# CM5_IO.net
KiCad netlist of a schematic drawn in Altium Designer
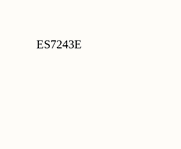
[diagram p0: CM5 + IO.SchDoc, top left]
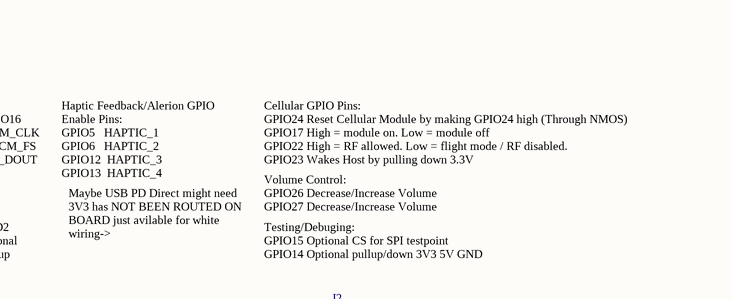
[diagram p1: CM5 + IO.SchDoc, top right]
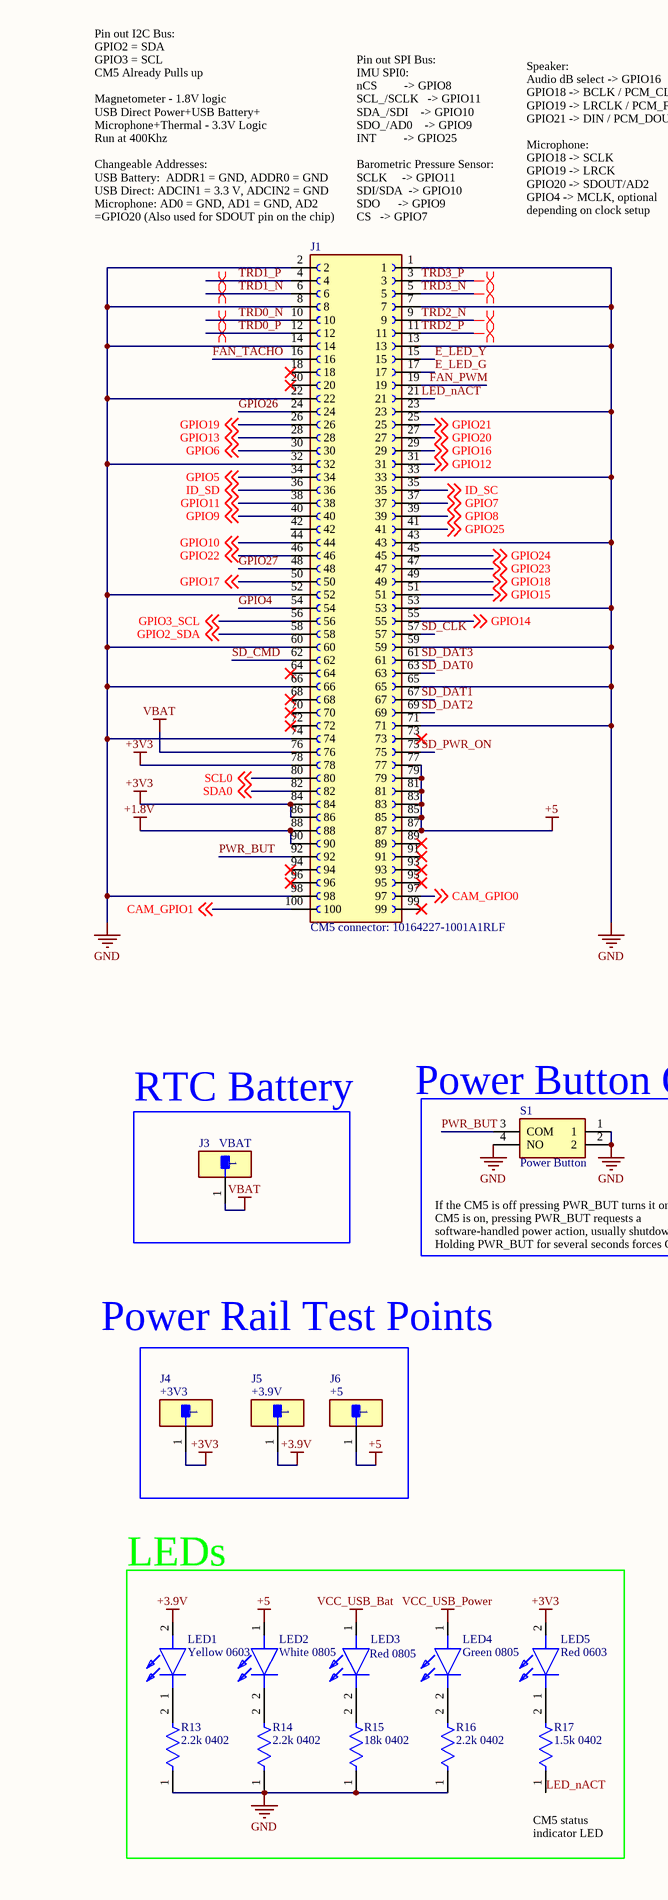
[diagram p2: CM5 + IO.SchDoc, bottom left]
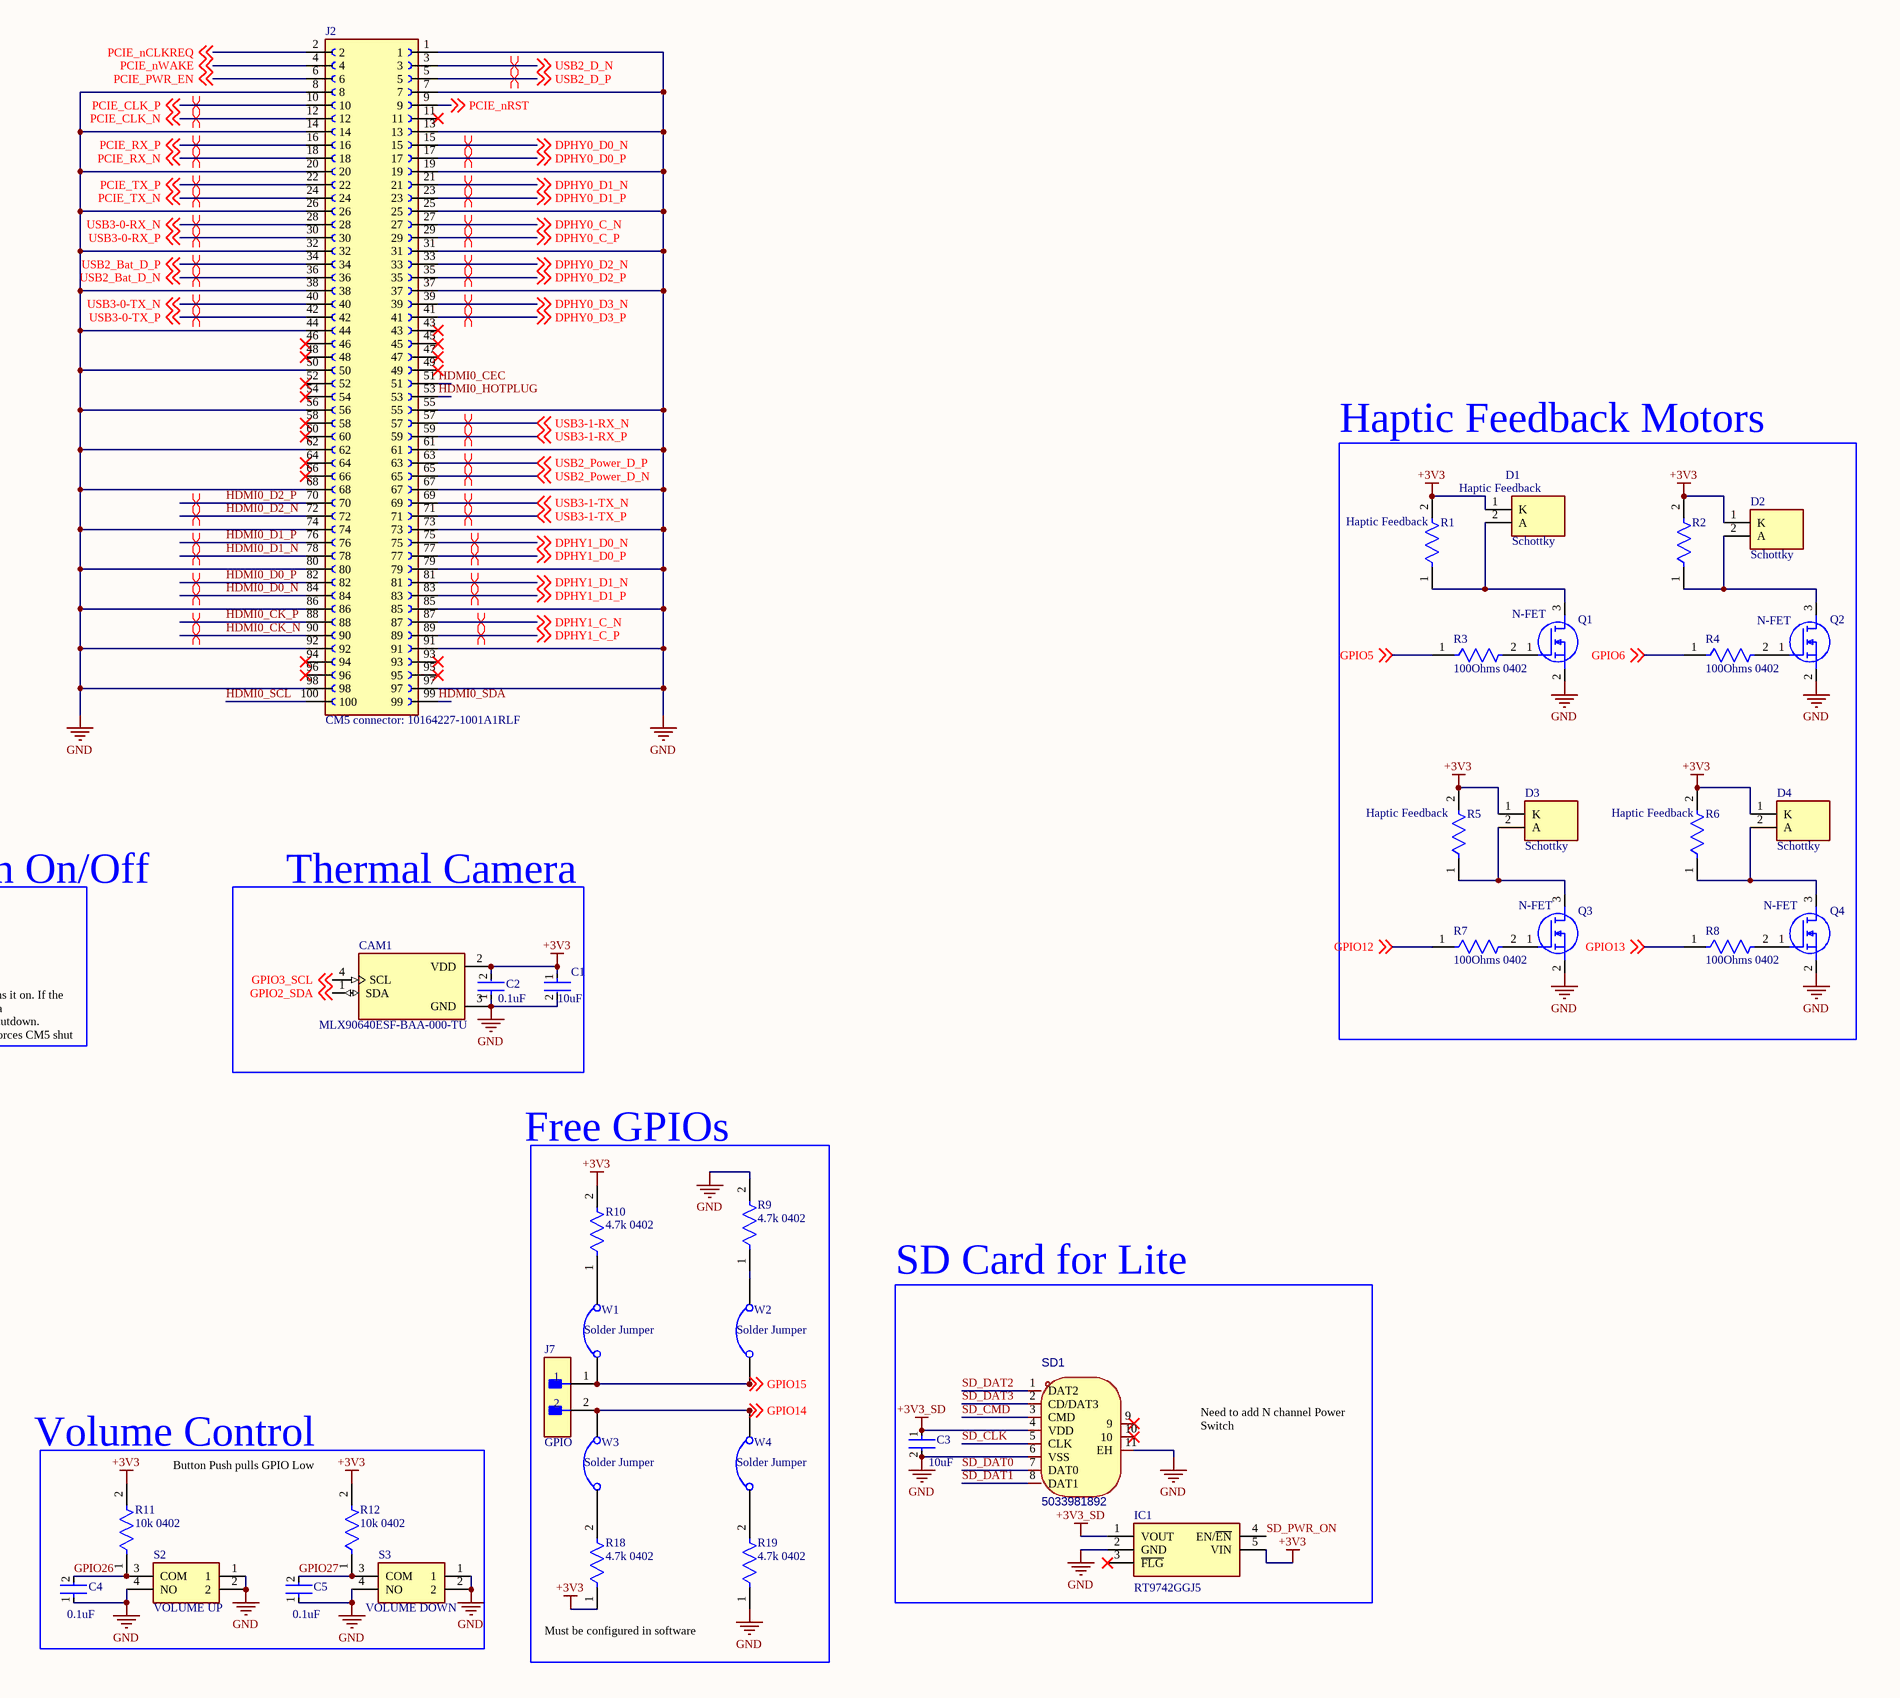
[diagram p3: CM5 + IO.SchDoc, bottom right]

(export (version "E")
  (design (tool "Eeschema 10.0.6"))
  (components
    (comp (ref "C1")
      (value "10uF")
      (footprint "FP-CC0603-DC-MFG")
      (description "C96446")
      (fields (field (name "TOLERANCE") "10%"))
      (libsource (lib "Altium Content Vault") (part "b4654b650e69147ec39a6b967a45e02"))
    )
    (comp (ref "C2")
      (value "0.1uF")
      (footprint "FP-C0402-BB-MFG")
      (description "C307331")
      (fields
        (field (name "TOLERANCE") "0.2")
        (field (name "OCTOPART") "https://octopart.com/c0402c104m3pac7867-kemet-84304880")
      )
      (libsource (lib "Altium Content Vault") (part "b4654b650e69147ec39a6b967a45e02"))
    )
    (comp (ref "C3")
      (value "10uF")
      (footprint "FP-CC0603-DC-MFG")
      (description "C96446")
      (fields (field (name "TOLERANCE") "10%"))
      (libsource (lib "Altium Content Vault") (part "b4654b650e69147ec39a6b967a45e02"))
    )
    (comp (ref "C4")
      (value "0.1uF")
      (footprint "FP-C0402-BB-MFG")
      (description "C307331")
      (fields
        (field (name "TOLERANCE") "0.2")
        (field (name "OCTOPART") "https://octopart.com/c0402c104m3pac7867-kemet-84304880")
      )
      (libsource (lib "Altium Content Vault") (part "b4654b650e69147ec39a6b967a45e02"))
    )
    (comp (ref "C5")
      (value "0.1uF")
      (footprint "FP-C0402-BB-MFG")
      (description "C307331")
      (fields
        (field (name "TOLERANCE") "0.2")
        (field (name "OCTOPART") "https://octopart.com/c0402c104m3pac7867-kemet-84304880")
      )
      (libsource (lib "Altium Content Vault") (part "b4654b650e69147ec39a6b967a45e02"))
    )
    (comp (ref "CAM1")
      (value "MLX90640ESF-BAA-000-TU")
      (footprint "TO292P930H600-4")
      (description "LCSC do not place\r\nBuy from digikey: MLX90640ESF-BAA-000-SP")
      (fields (field (name "MF") "Melexis Technologies"))
      (libsource (lib "Schlib1") (part "MLX90640ESF-BAA-000-TU"))
    )
    (comp (ref "D1")
      (value "Schottky")
      (footprint "PcbLib1:SOD2513X120N")
      (description "C7502696")
      (fields (field (name "MANUFACTURER_PART_NUMBER") "B0520WS-7-F"))
      (libsource (lib "*") (part "B0520WS-7-F"))
    )
    (comp (ref "D2")
      (value "Schottky")
      (footprint "PcbLib1:SOD2513X120N")
      (description "C7502696")
      (fields (field (name "MANUFACTURER_PART_NUMBER") "B0520WS-7-F"))
      (libsource (lib "*") (part "B0520WS-7-F"))
    )
    (comp (ref "D3")
      (value "Schottky")
      (footprint "PcbLib1:SOD2513X120N")
      (description "C7502696")
      (fields (field (name "MANUFACTURER_PART_NUMBER") "B0520WS-7-F"))
      (libsource (lib "*") (part "B0520WS-7-F"))
    )
    (comp (ref "D4")
      (value "Schottky")
      (footprint "PcbLib1:SOD2513X120N")
      (description "C7502696")
      (fields (field (name "MANUFACTURER_PART_NUMBER") "B0520WS-7-F"))
      (libsource (lib "*") (part "B0520WS-7-F"))
    )
    (comp (ref "IC1")
      (value "RT9742GGJ5")
      (footprint "PcbLib1:SOT94P280X100-5N")
      (description "C250547")
      (fields (field (name "MOUSER PART NUMBER") "835-RT9742GGJ5"))
      (libsource (lib "*") (part "RT9742GGJ5"))
    )
    (comp (ref "J1")
      (value "CM5 connector: 10164227-1001A1RLF")
      (footprint "Correct AMPHENOL_10164227-1001A1RLF")
      (description "C597931")
      (fields (field (name "MF") "Amphenol") (field (name "MP") "101642271001A1RLF"))
      (libsource (lib "Schlib1") (part "CM5 connector{colon} 10164227-1001A1RLF"))
    )
    (comp (ref "J2")
      (value "CM5 connector: 10164227-1001A1RLF")
      (footprint "Correct AMPHENOL_10164227-1001A1RLF")
      (description "C597931")
      (fields (field (name "MF") "Amphenol") (field (name "MP") "101642271001A1RLF"))
      (libsource (lib "Schlib1") (part "CM5 connector{colon} 10164227-1001A1RLF"))
    )
    (comp (ref "J3")
      (value "VBAT")
      (footprint "FP-TSW-101-07-L-S-MFG")
      (description "CONN HEADER VERT 1POS")
      (libsource (lib "Altium Content Vault") (part "dd45045ce8184df9e99e12baf3f412c"))
    )
    (comp (ref "J4")
      (value "+3V3")
      (footprint "FP-5015-MFG")
      (description "PC TEST POINT MINIATURE")
      (fields (field (name "MANUFACTURER PART NUMBER") "5015") (field (name "MANUFACTURER") "keystone"))
      (libsource (lib "Altium Content Vault") (part "dd45045ce8184df9e99e12baf3f412c"))
    )
    (comp (ref "J5")
      (value "+3.9V")
      (footprint "FP-5015-MFG")
      (description "PC TEST POINT MINIATURE")
      (fields (field (name "MANUFACTURER PART NUMBER") "5015") (field (name "MANUFACTURER") "keystone"))
      (libsource (lib "Altium Content Vault") (part "dd45045ce8184df9e99e12baf3f412c"))
    )
    (comp (ref "J6")
      (value "+5")
      (footprint "FP-5015-MFG")
      (description "PC TEST POINT MINIATURE")
      (fields (field (name "MANUFACTURER PART NUMBER") "5015") (field (name "MANUFACTURER") "keystone"))
      (libsource (lib "Altium Content Vault") (part "dd45045ce8184df9e99e12baf3f412c"))
    )
    (comp (ref "J7")
      (value "GPIO")
      (footprint "FP-TSW-102-07-F-S-MFG")
      (description "CONN HEADER VERT 2POS 2.54MM")
      (libsource (lib "Altium Content Vault") (part "3bc925449376181038e59eaffc5286c"))
    )
    (comp (ref "LED1")
      (value "Yellow 0603")
      (footprint "SamacSys:LEDC1608X70N")
      (description "C89811")
      (fields (field (name "MANUFACTURER_PART_NUMBER") "KT-0603R"))
      (libsource (lib "*") (part "KT-0603R"))
    )
    (comp (ref "LED2")
      (value "White 0805")
      (footprint "SamacSys:KT0805G")
      (description "C34499")
      (fields (field (name "MANUFACTURER_PART_NUMBER") "KT-0805G"))
      (libsource (lib "*") (part "KT-0805G"))
    )
    (comp (ref "LED3")
      (value "Red 0805")
      (footprint "SamacSys:KT0805G")
      (description "C84256")
      (fields (field (name "MANUFACTURER_PART_NUMBER") "KT-0805G"))
      (libsource (lib "*") (part "KT-0805G"))
    )
    (comp (ref "LED4")
      (value "Green 0805")
      (footprint "SamacSys:KT0805G")
      (description "C2297")
      (fields (field (name "MANUFACTURER_PART_NUMBER") "KT-0805G"))
      (libsource (lib "*") (part "KT-0805G"))
    )
    (comp (ref "LED5")
      (value "Red 0603")
      (footprint "SamacSys:LEDC1608X70N")
      (description "C2286")
      (fields (field (name "MANUFACTURER_PART_NUMBER") "KT-0603R"))
      (libsource (lib "*") (part "KT-0603R"))
    )
    (comp (ref "Q1")
      (value "N-FET")
      (footprint "PcbLib1:SOT95P280X125-3N")
      (description "C20917")
      (fields (field (name "MANUFACTURER_PART_NUMBER") "AO3400A"))
      (libsource (lib "*") (part "AO3400A"))
    )
    (comp (ref "Q2")
      (value "N-FET")
      (footprint "PcbLib1:SOT95P280X125-3N")
      (description "C20917")
      (fields (field (name "MANUFACTURER_PART_NUMBER") "AO3400A"))
      (libsource (lib "*") (part "AO3400A"))
    )
    (comp (ref "Q3")
      (value "N-FET")
      (footprint "PcbLib1:SOT95P280X125-3N")
      (description "C20917")
      (fields (field (name "MANUFACTURER_PART_NUMBER") "AO3400A"))
      (libsource (lib "*") (part "AO3400A"))
    )
    (comp (ref "Q4")
      (value "N-FET")
      (footprint "PcbLib1:SOT95P280X125-3N")
      (description "C20917")
      (fields (field (name "MANUFACTURER_PART_NUMBER") "AO3400A"))
      (libsource (lib "*") (part "AO3400A"))
    )
    (comp (ref "R1")
      (value "Haptic Feedback")
      (footprint "FP-RMCF1206-IPC_B")
      (description "DNP")
      (fields (field (name "TOLERANCE") "5%"))
      (libsource (lib "Altium Content Vault") (part "1029c3af85768c4190bb7ad29bc67b5"))
    )
    (comp (ref "R2")
      (value "Haptic Feedback")
      (footprint "FP-RMCF1206-IPC_B")
      (description "DNP")
      (fields (field (name "TOLERANCE") "5%"))
      (libsource (lib "Altium Content Vault") (part "1029c3af85768c4190bb7ad29bc67b5"))
    )
    (comp (ref "R3")
      (value "100Ohms 0402")
      (footprint "FP-RMCF0402-MFG")
      (description "C25076")
      (fields (field (name "TOLERANCE") "5%"))
      (libsource (lib "Altium Content Vault") (part "1029c3af85768c4190bb7ad29bc67b5"))
    )
    (comp (ref "R4")
      (value "100Ohms 0402")
      (footprint "FP-RMCF0402-MFG")
      (description "C25076")
      (fields (field (name "TOLERANCE") "5%"))
      (libsource (lib "Altium Content Vault") (part "1029c3af85768c4190bb7ad29bc67b5"))
    )
    (comp (ref "R5")
      (value "Haptic Feedback")
      (footprint "FP-RMCF1206-IPC_B")
      (description "DNP")
      (fields (field (name "TOLERANCE") "5%"))
      (libsource (lib "Altium Content Vault") (part "1029c3af85768c4190bb7ad29bc67b5"))
    )
    (comp (ref "R6")
      (value "Haptic Feedback")
      (footprint "FP-RMCF1206-IPC_B")
      (description "DNP")
      (fields (field (name "TOLERANCE") "5%"))
      (libsource (lib "Altium Content Vault") (part "1029c3af85768c4190bb7ad29bc67b5"))
    )
    (comp (ref "R7")
      (value "100Ohms 0402")
      (footprint "FP-RMCF0402-MFG")
      (description "C25076")
      (fields (field (name "TOLERANCE") "5%"))
      (libsource (lib "Altium Content Vault") (part "1029c3af85768c4190bb7ad29bc67b5"))
    )
    (comp (ref "R8")
      (value "100Ohms 0402")
      (footprint "FP-RMCF0402-MFG")
      (description "C25076")
      (fields (field (name "TOLERANCE") "5%"))
      (libsource (lib "Altium Content Vault") (part "1029c3af85768c4190bb7ad29bc67b5"))
    )
    (comp (ref "R9")
      (value "4.7k 0402")
      (footprint "FP-RMCF0402-MFG")
      (description "C25900")
      (fields (field (name "TOLERANCE") "5%"))
      (libsource (lib "Altium Content Vault") (part "1029c3af85768c4190bb7ad29bc67b5"))
    )
    (comp (ref "R10")
      (value "4.7k 0402")
      (footprint "FP-RMCF0402-MFG")
      (description "C25900")
      (fields (field (name "TOLERANCE") "5%"))
      (libsource (lib "Altium Content Vault") (part "1029c3af85768c4190bb7ad29bc67b5"))
    )
    (comp (ref "R11")
      (value "10k 0402")
      (footprint "FP-RMCF0402-MFG")
      (description "C25744")
      (fields (field (name "TOLERANCE") "5%"))
      (libsource (lib "Altium Content Vault") (part "1029c3af85768c4190bb7ad29bc67b5"))
    )
    (comp (ref "R12")
      (value "10k 0402")
      (footprint "FP-RMCF0402-MFG")
      (description "C25744")
      (fields (field (name "TOLERANCE") "5%"))
      (libsource (lib "Altium Content Vault") (part "1029c3af85768c4190bb7ad29bc67b5"))
    )
    (comp (ref "R13")
      (value "2.2k 0402")
      (footprint "FP-AF0402-IPC_B")
      (description "C25879")
      (fields (field (name "TOLERANCE") "5%"))
      (libsource (lib "Altium Content Vault") (part "1029c3af85768c4190bb7ad29bc67b5"))
    )
    (comp (ref "R14")
      (value "2.2k 0402")
      (footprint "FP-AF0402-IPC_B")
      (description "C25879")
      (fields (field (name "TOLERANCE") "5%"))
      (libsource (lib "Altium Content Vault") (part "1029c3af85768c4190bb7ad29bc67b5"))
    )
    (comp (ref "R15")
      (value "18k 0402")
      (footprint "FP-AF0402-IPC_B")
      (description "C25762")
      (fields (field (name "TOLERANCE") "5%"))
      (libsource (lib "Altium Content Vault") (part "1029c3af85768c4190bb7ad29bc67b5"))
    )
    (comp (ref "R16")
      (value "2.2k 0402")
      (footprint "FP-AF0402-IPC_B")
      (description "C25879")
      (fields (field (name "TOLERANCE") "5%"))
      (libsource (lib "Altium Content Vault") (part "1029c3af85768c4190bb7ad29bc67b5"))
    )
    (comp (ref "R17")
      (value "1.5k 0402")
      (footprint "FP-AF0402-IPC_B")
      (description "C25867")
      (fields (field (name "TOLERANCE") "5%"))
      (libsource (lib "Altium Content Vault") (part "1029c3af85768c4190bb7ad29bc67b5"))
    )
    (comp (ref "R18")
      (value "4.7k 0402")
      (footprint "FP-RMCF0402-MFG")
      (description "C25900")
      (fields (field (name "TOLERANCE") "5%"))
      (libsource (lib "Altium Content Vault") (part "1029c3af85768c4190bb7ad29bc67b5"))
    )
    (comp (ref "R19")
      (value "4.7k 0402")
      (footprint "FP-RMCF0402-MFG")
      (description "C25900")
      (fields (field (name "TOLERANCE") "5%"))
      (libsource (lib "Altium Content Vault") (part "1029c3af85768c4190bb7ad29bc67b5"))
    )
    (comp (ref "S1")
      (value "Power Button")
      (footprint "PcbLib1:TS24CA")
      (description "C393942")
      (fields (field (name "MANUFACTURER_PART_NUMBER") "TS24CA"))
      (libsource (lib "*") (part "TS24CA"))
    )
    (comp (ref "S2")
      (value "VOLUME UP")
      (footprint "PcbLib1:TS24CA")
      (description "C393942")
      (fields (field (name "MANUFACTURER_PART_NUMBER") "TS24CA"))
      (libsource (lib "*") (part "TS24CA"))
    )
    (comp (ref "S3")
      (value "VOLUME DOWN")
      (footprint "PcbLib1:TS24CA")
      (description "C393942")
      (fields (field (name "MANUFACTURER_PART_NUMBER") "TS24CA"))
      (libsource (lib "*") (part "TS24CA"))
    )
    (comp (ref "SD1")
      (value "5033981892")
      (footprint "TF-SMD_503398-1892")
      (description "C5362198")
      (fields (field (name "MANUFACTURER") "MOLEX"))
      (libsource (lib "Schlib1") (part "SD Card"))
    )
    (comp (ref "W1")
      (value "Solder Jumper")
      (footprint "Solder Bridge")
      (description "DNP")
      (fields (field (name "MF") "Keystone Electronics") (field (name "MP") "5102"))
      (libsource (lib "Schlib1") (part "Solder Jumper"))
    )
    (comp (ref "W2")
      (value "Solder Jumper")
      (footprint "Solder Bridge")
      (description "DNP")
      (fields (field (name "MF") "Keystone Electronics") (field (name "MP") "5102"))
      (libsource (lib "Schlib1") (part "Solder Jumper"))
    )
    (comp (ref "W3")
      (value "Solder Jumper")
      (footprint "Solder Bridge")
      (description "DNP")
      (fields (field (name "MF") "Keystone Electronics") (field (name "MP") "5102"))
      (libsource (lib "Schlib1") (part "Solder Jumper"))
    )
    (comp (ref "W4")
      (value "Solder Jumper")
      (footprint "Solder Bridge")
      (description "DNP")
      (fields (field (name "MF") "Keystone Electronics") (field (name "MP") "5102"))
      (libsource (lib "Schlib1") (part "Solder Jumper"))
    )
  )
  (nets
    (net (code "1") (name "+1.8V") (class "Default")
      (node (ref "J1") (pin "88") (pinfunction "88_88") (pintype "passive"))
      (node (ref "J1") (pin "90") (pinfunction "90_90") (pintype "passive"))
    )
    (net (code "2") (name "+3.9V") (class "Default")
      (node (ref "J5") (pin "1") (pinfunction "1_1") (pintype "passive"))
      (node (ref "LED1") (pin "2") (pinfunction "A_2") (pintype "passive"))
    )
    (net (code "3") (name "+3V3") (class "Default")
      (node (ref "C1") (pin "1") (pinfunction "1_1") (pintype "passive"))
      (node (ref "C2") (pin "2") (pinfunction "2_2") (pintype "passive"))
      (node (ref "CAM1") (pin "2") (pinfunction "VDD_2") (pintype "power_in"))
      (node (ref "D1") (pin "1") (pinfunction "K_1") (pintype "passive"))
      (node (ref "D2") (pin "1") (pinfunction "K_1") (pintype "passive"))
      (node (ref "D3") (pin "1") (pinfunction "K_1") (pintype "passive"))
      (node (ref "D4") (pin "1") (pinfunction "K_1") (pintype "passive"))
      (node (ref "IC1") (pin "5") (pinfunction "VIN_5") (pintype "passive"))
      (node (ref "J1") (pin "78") (pinfunction "78_78") (pintype "passive"))
      (node (ref "J1") (pin "84") (pinfunction "84_84") (pintype "passive"))
      (node (ref "J1") (pin "86") (pinfunction "86_86") (pintype "passive"))
      (node (ref "J4") (pin "1") (pinfunction "1_1") (pintype "passive"))
      (node (ref "LED5") (pin "2") (pinfunction "A_2") (pintype "passive"))
      (node (ref "R1") (pin "2") (pinfunction "2_2") (pintype "passive"))
      (node (ref "R10") (pin "2") (pinfunction "2_2") (pintype "passive"))
      (node (ref "R11") (pin "2") (pinfunction "2_2") (pintype "passive"))
      (node (ref "R12") (pin "2") (pinfunction "2_2") (pintype "passive"))
      (node (ref "R18") (pin "1") (pinfunction "1_1") (pintype "passive"))
      (node (ref "R2") (pin "2") (pinfunction "2_2") (pintype "passive"))
      (node (ref "R5") (pin "2") (pinfunction "2_2") (pintype "passive"))
      (node (ref "R6") (pin "2") (pinfunction "2_2") (pintype "passive"))
    )
    (net (code "4") (name "+3V3_SD") (class "Default")
      (node (ref "C3") (pin "1") (pinfunction "1_1") (pintype "passive"))
      (node (ref "IC1") (pin "1") (pinfunction "VOUT_1") (pintype "passive"))
      (node (ref "SD1") (pin "4") (pinfunction "VDD_4") (pintype "passive"))
    )
    (net (code "5") (name "+5") (class "Default")
      (node (ref "J1") (pin "77") (pinfunction "77_77") (pintype "passive"))
      (node (ref "J1") (pin "79") (pinfunction "79_79") (pintype "passive"))
      (node (ref "J1") (pin "81") (pinfunction "81_81") (pintype "passive"))
      (node (ref "J1") (pin "83") (pinfunction "83_83") (pintype "passive"))
      (node (ref "J1") (pin "85") (pinfunction "85_85") (pintype "passive"))
      (node (ref "J1") (pin "87") (pinfunction "87_87") (pintype "passive"))
      (node (ref "J6") (pin "1") (pinfunction "1_1") (pintype "passive"))
      (node (ref "LED2") (pin "1") (pinfunction "A_1") (pintype "passive"))
    )
    (net (code "6") (name "/E_LED_G") (class "Default")
      (node (ref "J1") (pin "17") (pinfunction "17_17") (pintype "passive"))
    )
    (net (code "7") (name "/E_LED_Y") (class "Default")
      (node (ref "J1") (pin "15") (pinfunction "15_15") (pintype "passive"))
    )
    (net (code "8") (name "/FAN_PWM") (class "Default")
      (node (ref "J1") (pin "19") (pinfunction "19_19") (pintype "passive"))
    )
    (net (code "9") (name "/FAN_TACHO") (class "Default")
      (node (ref "J1") (pin "16") (pinfunction "16_16") (pintype "passive"))
    )
    (net (code "10") (name "/GPIO4") (class "Default")
      (node (ref "J1") (pin "54") (pinfunction "54_54") (pintype "passive"))
    )
    (net (code "11") (name "/GPIO26") (class "Default")
      (node (ref "C4") (pin "2") (pinfunction "2_2") (pintype "passive"))
      (node (ref "J1") (pin "24") (pinfunction "24_24") (pintype "passive"))
      (node (ref "R11") (pin "1") (pinfunction "1_1") (pintype "passive"))
      (node (ref "S2") (pin "3") (pinfunction "COM_3") (pintype "passive"))
    )
    (net (code "12") (name "/GPIO27") (class "Default")
      (node (ref "C5") (pin "2") (pinfunction "2_2") (pintype "passive"))
      (node (ref "J1") (pin "48") (pinfunction "48_48") (pintype "passive"))
      (node (ref "R12") (pin "1") (pinfunction "1_1") (pintype "passive"))
      (node (ref "S3") (pin "3") (pinfunction "COM_3") (pintype "passive"))
    )
    (net (code "13") (name "/HDMI0_CEC") (class "Default")
      (node (ref "J2") (pin "51") (pinfunction "51_51") (pintype "passive"))
    )
    (net (code "14") (name "/HDMI0_CK_N") (class "Default")
      (node (ref "J2") (pin "90") (pinfunction "90_90") (pintype "passive"))
    )
    (net (code "15") (name "/HDMI0_CK_P") (class "Default")
      (node (ref "J2") (pin "88") (pinfunction "88_88") (pintype "passive"))
    )
    (net (code "16") (name "/HDMI0_D0_N") (class "Default")
      (node (ref "J2") (pin "84") (pinfunction "84_84") (pintype "passive"))
    )
    (net (code "17") (name "/HDMI0_D0_P") (class "Default")
      (node (ref "J2") (pin "82") (pinfunction "82_82") (pintype "passive"))
    )
    (net (code "18") (name "/HDMI0_D1_N") (class "Default")
      (node (ref "J2") (pin "78") (pinfunction "78_78") (pintype "passive"))
    )
    (net (code "19") (name "/HDMI0_D1_P") (class "Default")
      (node (ref "J2") (pin "76") (pinfunction "76_76") (pintype "passive"))
    )
    (net (code "20") (name "/HDMI0_D2_N") (class "Default")
      (node (ref "J2") (pin "72") (pinfunction "72_72") (pintype "passive"))
    )
    (net (code "21") (name "/HDMI0_D2_P") (class "Default")
      (node (ref "J2") (pin "70") (pinfunction "70_70") (pintype "passive"))
    )
    (net (code "22") (name "/HDMI0_HOTPLUG") (class "Default")
      (node (ref "J2") (pin "53") (pinfunction "53_53") (pintype "passive"))
    )
    (net (code "23") (name "/HDMI0_SCL") (class "Default")
      (node (ref "J2") (pin "100") (pinfunction "100_100") (pintype "passive"))
    )
    (net (code "24") (name "/HDMI0_SDA") (class "Default")
      (node (ref "J2") (pin "99") (pinfunction "99_99") (pintype "passive"))
    )
    (net (code "25") (name "/LED_nACT") (class "Default")
      (node (ref "J1") (pin "21") (pinfunction "21_21") (pintype "passive"))
      (node (ref "R17") (pin "1") (pinfunction "1_1") (pintype "passive"))
    )
    (net (code "26") (name "/PWR_BUT") (class "Default")
      (node (ref "J1") (pin "92") (pinfunction "92_92") (pintype "passive"))
      (node (ref "S1") (pin "3") (pinfunction "COM_3") (pintype "passive"))
    )
    (net (code "27") (name "/SD_CLK") (class "Default")
      (node (ref "J1") (pin "57") (pinfunction "57_57") (pintype "passive"))
      (node (ref "SD1") (pin "5") (pinfunction "CLK_5") (pintype "passive"))
    )
    (net (code "28") (name "/SD_CMD") (class "Default")
      (node (ref "J1") (pin "62") (pinfunction "62_62") (pintype "passive"))
      (node (ref "SD1") (pin "3") (pinfunction "CMD_3") (pintype "passive"))
    )
    (net (code "29") (name "/SD_DAT0") (class "Default")
      (node (ref "J1") (pin "63") (pinfunction "63_63") (pintype "passive"))
      (node (ref "SD1") (pin "7") (pinfunction "DAT0_7") (pintype "passive"))
    )
    (net (code "30") (name "/SD_DAT1") (class "Default")
      (node (ref "J1") (pin "67") (pinfunction "67_67") (pintype "passive"))
      (node (ref "SD1") (pin "8") (pinfunction "DAT1_8") (pintype "passive"))
    )
    (net (code "31") (name "/SD_DAT2") (class "Default")
      (node (ref "J1") (pin "69") (pinfunction "69_69") (pintype "passive"))
      (node (ref "SD1") (pin "1") (pinfunction "DAT2_1") (pintype "passive"))
    )
    (net (code "32") (name "/SD_DAT3") (class "Default")
      (node (ref "J1") (pin "61") (pinfunction "61_61") (pintype "passive"))
      (node (ref "SD1") (pin "2") (pinfunction "CD/DAT3_2") (pintype "passive"))
    )
    (net (code "33") (name "/SD_PWR_ON") (class "Default")
      (node (ref "IC1") (pin "4") (pinfunction "EN/~{EN}_4") (pintype "passive"))
      (node (ref "J1") (pin "75") (pinfunction "75_75") (pintype "passive"))
    )
    (net (code "34") (name "/TRD0_N") (class "Default")
      (node (ref "J1") (pin "10") (pinfunction "10_10") (pintype "passive"))
    )
    (net (code "35") (name "/TRD0_P") (class "Default")
      (node (ref "J1") (pin "12") (pinfunction "12_12") (pintype "passive"))
    )
    (net (code "36") (name "/TRD1_N") (class "Default")
      (node (ref "J1") (pin "6") (pinfunction "6_6") (pintype "passive"))
    )
    (net (code "37") (name "/TRD1_P") (class "Default")
      (node (ref "J1") (pin "4") (pinfunction "4_4") (pintype "passive"))
    )
    (net (code "38") (name "/TRD2_N") (class "Default")
      (node (ref "J1") (pin "9") (pinfunction "9_9") (pintype "passive"))
    )
    (net (code "39") (name "/TRD2_P") (class "Default")
      (node (ref "J1") (pin "11") (pinfunction "11_11") (pintype "passive"))
    )
    (net (code "40") (name "/TRD3_N") (class "Default")
      (node (ref "J1") (pin "5") (pinfunction "5_5") (pintype "passive"))
    )
    (net (code "41") (name "/TRD3_P") (class "Default")
      (node (ref "J1") (pin "3") (pinfunction "3_3") (pintype "passive"))
    )
    (net (code "42") (name "CAM_GPIO0") (class "Default")
      (node (ref "J1") (pin "97") (pinfunction "97_97") (pintype "passive"))
    )
    (net (code "43") (name "CAM_GPIO1") (class "Default")
      (node (ref "J1") (pin "100") (pinfunction "100_100") (pintype "passive"))
    )
    (net (code "44") (name "DPHY0_C_N") (class "Default")
      (node (ref "J2") (pin "27") (pinfunction "27_27") (pintype "passive"))
    )
    (net (code "45") (name "DPHY0_C_P") (class "Default")
      (node (ref "J2") (pin "29") (pinfunction "29_29") (pintype "passive"))
    )
    (net (code "46") (name "DPHY0_D0_N") (class "Default")
      (node (ref "J2") (pin "15") (pinfunction "15_15") (pintype "passive"))
    )
    (net (code "47") (name "DPHY0_D0_P") (class "Default")
      (node (ref "J2") (pin "17") (pinfunction "17_17") (pintype "passive"))
    )
    (net (code "48") (name "DPHY0_D1_N") (class "Default")
      (node (ref "J2") (pin "21") (pinfunction "21_21") (pintype "passive"))
    )
    (net (code "49") (name "DPHY0_D1_P") (class "Default")
      (node (ref "J2") (pin "23") (pinfunction "23_23") (pintype "passive"))
    )
    (net (code "50") (name "DPHY0_D2_N") (class "Default")
      (node (ref "J2") (pin "33") (pinfunction "33_33") (pintype "passive"))
    )
    (net (code "51") (name "DPHY0_D2_P") (class "Default")
      (node (ref "J2") (pin "35") (pinfunction "35_35") (pintype "passive"))
    )
    (net (code "52") (name "DPHY0_D3_N") (class "Default")
      (node (ref "J2") (pin "39") (pinfunction "39_39") (pintype "passive"))
    )
    (net (code "53") (name "DPHY0_D3_P") (class "Default")
      (node (ref "J2") (pin "41") (pinfunction "41_41") (pintype "passive"))
    )
    (net (code "54") (name "DPHY1_C_N") (class "Default")
      (node (ref "J2") (pin "87") (pinfunction "87_87") (pintype "passive"))
    )
    (net (code "55") (name "DPHY1_C_P") (class "Default")
      (node (ref "J2") (pin "89") (pinfunction "89_89") (pintype "passive"))
    )
    (net (code "56") (name "DPHY1_D0_N") (class "Default")
      (node (ref "J2") (pin "75") (pinfunction "75_75") (pintype "passive"))
    )
    (net (code "57") (name "DPHY1_D0_P") (class "Default")
      (node (ref "J2") (pin "77") (pinfunction "77_77") (pintype "passive"))
    )
    (net (code "58") (name "DPHY1_D1_N") (class "Default")
      (node (ref "J2") (pin "81") (pinfunction "81_81") (pintype "passive"))
    )
    (net (code "59") (name "DPHY1_D1_P") (class "Default")
      (node (ref "J2") (pin "83") (pinfunction "83_83") (pintype "passive"))
    )
    (net (code "60") (name "GND") (class "Default")
      (node (ref "C1") (pin "2") (pinfunction "2_2") (pintype "passive"))
      (node (ref "C2") (pin "1") (pinfunction "1_1") (pintype "passive"))
      (node (ref "C3") (pin "2") (pinfunction "2_2") (pintype "passive"))
      (node (ref "C4") (pin "1") (pinfunction "1_1") (pintype "passive"))
      (node (ref "C5") (pin "1") (pinfunction "1_1") (pintype "passive"))
      (node (ref "CAM1") (pin "3") (pinfunction "GND_3") (pintype "power_in"))
      (node (ref "IC1") (pin "2") (pinfunction "GND_2") (pintype "passive"))
      (node (ref "J1") (pin "1") (pinfunction "1_1") (pintype "passive"))
      (node (ref "J1") (pin "13") (pinfunction "13_13") (pintype "passive"))
      (node (ref "J1") (pin "14") (pinfunction "14_14") (pintype "passive"))
      (node (ref "J1") (pin "2") (pinfunction "2_2") (pintype "passive"))
      (node (ref "J1") (pin "22") (pinfunction "22_22") (pintype "passive"))
      (node (ref "J1") (pin "23") (pinfunction "23_23") (pintype "passive"))
      (node (ref "J1") (pin "32") (pinfunction "32_32") (pintype "passive"))
      (node (ref "J1") (pin "33") (pinfunction "33_33") (pintype "passive"))
      (node (ref "J1") (pin "43") (pinfunction "43_43") (pintype "passive"))
      (node (ref "J1") (pin "52") (pinfunction "52_52") (pintype "passive"))
      (node (ref "J1") (pin "53") (pinfunction "53_53") (pintype "passive"))
      (node (ref "J1") (pin "59") (pinfunction "59_59") (pintype "passive"))
      (node (ref "J1") (pin "60") (pinfunction "60_60") (pintype "passive"))
      (node (ref "J1") (pin "65") (pinfunction "65_65") (pintype "passive"))
      (node (ref "J1") (pin "66") (pinfunction "66_66") (pintype "passive"))
      (node (ref "J1") (pin "7") (pinfunction "7_7") (pintype "passive"))
      (node (ref "J1") (pin "71") (pinfunction "71_71") (pintype "passive"))
      (node (ref "J1") (pin "74") (pinfunction "74_74") (pintype "passive"))
      (node (ref "J1") (pin "8") (pinfunction "8_8") (pintype "passive"))
      (node (ref "J1") (pin "98") (pinfunction "98_98") (pintype "passive"))
      (node (ref "J2") (pin "1") (pinfunction "1_1") (pintype "passive"))
      (node (ref "J2") (pin "13") (pinfunction "13_13") (pintype "passive"))
      (node (ref "J2") (pin "14") (pinfunction "14_14") (pintype "passive"))
      (node (ref "J2") (pin "19") (pinfunction "19_19") (pintype "passive"))
      (node (ref "J2") (pin "20") (pinfunction "20_20") (pintype "passive"))
      (node (ref "J2") (pin "25") (pinfunction "25_25") (pintype "passive"))
      (node (ref "J2") (pin "26") (pinfunction "26_26") (pintype "passive"))
      (node (ref "J2") (pin "31") (pinfunction "31_31") (pintype "passive"))
      (node (ref "J2") (pin "32") (pinfunction "32_32") (pintype "passive"))
      (node (ref "J2") (pin "37") (pinfunction "37_37") (pintype "passive"))
      (node (ref "J2") (pin "38") (pinfunction "38_38") (pintype "passive"))
      (node (ref "J2") (pin "44") (pinfunction "44_44") (pintype "passive"))
      (node (ref "J2") (pin "50") (pinfunction "50_50") (pintype "passive"))
      (node (ref "J2") (pin "55") (pinfunction "55_55") (pintype "passive"))
      (node (ref "J2") (pin "56") (pinfunction "56_56") (pintype "passive"))
      (node (ref "J2") (pin "61") (pinfunction "61_61") (pintype "passive"))
      (node (ref "J2") (pin "62") (pinfunction "62_62") (pintype "passive"))
      (node (ref "J2") (pin "67") (pinfunction "67_67") (pintype "passive"))
      (node (ref "J2") (pin "68") (pinfunction "68_68") (pintype "passive"))
      (node (ref "J2") (pin "7") (pinfunction "7_7") (pintype "passive"))
      (node (ref "J2") (pin "73") (pinfunction "73_73") (pintype "passive"))
      (node (ref "J2") (pin "74") (pinfunction "74_74") (pintype "passive"))
      (node (ref "J2") (pin "79") (pinfunction "79_79") (pintype "passive"))
      (node (ref "J2") (pin "8") (pinfunction "8_8") (pintype "passive"))
      (node (ref "J2") (pin "80") (pinfunction "80_80") (pintype "passive"))
      (node (ref "J2") (pin "85") (pinfunction "85_85") (pintype "passive"))
      (node (ref "J2") (pin "86") (pinfunction "86_86") (pintype "passive"))
      (node (ref "J2") (pin "91") (pinfunction "91_91") (pintype "passive"))
      (node (ref "J2") (pin "92") (pinfunction "92_92") (pintype "passive"))
      (node (ref "J2") (pin "97") (pinfunction "97_97") (pintype "passive"))
      (node (ref "J2") (pin "98") (pinfunction "98_98") (pintype "passive"))
      (node (ref "Q1") (pin "2") (pinfunction "S_2") (pintype "passive"))
      (node (ref "Q2") (pin "2") (pinfunction "S_2") (pintype "passive"))
      (node (ref "Q3") (pin "2") (pinfunction "S_2") (pintype "passive"))
      (node (ref "Q4") (pin "2") (pinfunction "S_2") (pintype "passive"))
      (node (ref "R13") (pin "1") (pinfunction "1_1") (pintype "passive"))
      (node (ref "R14") (pin "1") (pinfunction "1_1") (pintype "passive"))
      (node (ref "R15") (pin "1") (pinfunction "1_1") (pintype "passive"))
      (node (ref "R16") (pin "1") (pinfunction "1_1") (pintype "passive"))
      (node (ref "R19") (pin "1") (pinfunction "1_1") (pintype "passive"))
      (node (ref "R9") (pin "2") (pinfunction "2_2") (pintype "passive"))
      (node (ref "S1") (pin "1") (pinfunction "1_1") (pintype "passive"))
      (node (ref "S1") (pin "2") (pinfunction "2_2") (pintype "passive"))
      (node (ref "S1") (pin "4") (pinfunction "NO_4") (pintype "passive"))
      (node (ref "S2") (pin "1") (pinfunction "1_1") (pintype "passive"))
      (node (ref "S2") (pin "2") (pinfunction "2_2") (pintype "passive"))
      (node (ref "S2") (pin "4") (pinfunction "NO_4") (pintype "passive"))
      (node (ref "S3") (pin "1") (pinfunction "1_1") (pintype "passive"))
      (node (ref "S3") (pin "2") (pinfunction "2_2") (pintype "passive"))
      (node (ref "S3") (pin "4") (pinfunction "NO_4") (pintype "passive"))
      (node (ref "SD1") (pin "11") (pinfunction "EH_11") (pintype "passive"))
      (node (ref "SD1") (pin "6") (pinfunction "VSS_6") (pintype "passive"))
    )
    (net (code "61") (name "GPIO2_SDA") (class "Default")
      (node (ref "CAM1") (pin "1") (pinfunction "SDA_1") (pintype "bidirectional"))
      (node (ref "J1") (pin "58") (pinfunction "58_58") (pintype "passive"))
    )
    (net (code "62") (name "GPIO3_SCL") (class "Default")
      (node (ref "CAM1") (pin "4") (pinfunction "SCL_4") (pintype "input"))
      (node (ref "J1") (pin "56") (pinfunction "56_56") (pintype "passive"))
    )
    (net (code "63") (name "GPIO5") (class "Default")
      (node (ref "J1") (pin "34") (pinfunction "34_34") (pintype "passive"))
      (node (ref "R3") (pin "1") (pinfunction "1_1") (pintype "passive"))
    )
    (net (code "64") (name "GPIO6") (class "Default")
      (node (ref "J1") (pin "30") (pinfunction "30_30") (pintype "passive"))
      (node (ref "R4") (pin "1") (pinfunction "1_1") (pintype "passive"))
    )
    (net (code "65") (name "GPIO7") (class "Default")
      (node (ref "J1") (pin "37") (pinfunction "37_37") (pintype "passive"))
    )
    (net (code "66") (name "GPIO8") (class "Default")
      (node (ref "J1") (pin "39") (pinfunction "39_39") (pintype "passive"))
    )
    (net (code "67") (name "GPIO9") (class "Default")
      (node (ref "J1") (pin "40") (pinfunction "40_40") (pintype "passive"))
    )
    (net (code "68") (name "GPIO10") (class "Default")
      (node (ref "J1") (pin "44") (pinfunction "44_44") (pintype "passive"))
    )
    (net (code "69") (name "GPIO11") (class "Default")
      (node (ref "J1") (pin "38") (pinfunction "38_38") (pintype "passive"))
    )
    (net (code "70") (name "GPIO12") (class "Default")
      (node (ref "J1") (pin "31") (pinfunction "31_31") (pintype "passive"))
      (node (ref "R7") (pin "1") (pinfunction "1_1") (pintype "passive"))
    )
    (net (code "71") (name "GPIO13") (class "Default")
      (node (ref "J1") (pin "28") (pinfunction "28_28") (pintype "passive"))
      (node (ref "R8") (pin "1") (pinfunction "1_1") (pintype "passive"))
    )
    (net (code "72") (name "GPIO14") (class "Default")
      (node (ref "J1") (pin "55") (pinfunction "55_55") (pintype "passive"))
      (node (ref "J7") (pin "2") (pinfunction "2_2") (pintype "passive"))
      (node (ref "W3") (pin "2") (pinfunction "2_2") (pintype "passive"))
      (node (ref "W4") (pin "2") (pinfunction "2_2") (pintype "passive"))
    )
    (net (code "73") (name "GPIO15") (class "Default")
      (node (ref "J1") (pin "51") (pinfunction "51_51") (pintype "passive"))
      (node (ref "J7") (pin "1") (pinfunction "1_1") (pintype "passive"))
      (node (ref "W1") (pin "1") (pinfunction "1_1") (pintype "passive"))
      (node (ref "W2") (pin "1") (pinfunction "1_1") (pintype "passive"))
    )
    (net (code "74") (name "GPIO16") (class "Default")
      (node (ref "J1") (pin "29") (pinfunction "29_29") (pintype "passive"))
    )
    (net (code "75") (name "GPIO17") (class "Default")
      (node (ref "J1") (pin "50") (pinfunction "50_50") (pintype "passive"))
    )
    (net (code "76") (name "GPIO18") (class "Default")
      (node (ref "J1") (pin "49") (pinfunction "49_49") (pintype "passive"))
    )
    (net (code "77") (name "GPIO19") (class "Default")
      (node (ref "J1") (pin "26") (pinfunction "26_26") (pintype "passive"))
    )
    (net (code "78") (name "GPIO20") (class "Default")
      (node (ref "J1") (pin "27") (pinfunction "27_27") (pintype "passive"))
    )
    (net (code "79") (name "GPIO21") (class "Default")
      (node (ref "J1") (pin "25") (pinfunction "25_25") (pintype "passive"))
    )
    (net (code "80") (name "GPIO22") (class "Default")
      (node (ref "J1") (pin "46") (pinfunction "46_46") (pintype "passive"))
    )
    (net (code "81") (name "GPIO23") (class "Default")
      (node (ref "J1") (pin "47") (pinfunction "47_47") (pintype "passive"))
    )
    (net (code "82") (name "GPIO24") (class "Default")
      (node (ref "J1") (pin "45") (pinfunction "45_45") (pintype "passive"))
    )
    (net (code "83") (name "GPIO25") (class "Default")
      (node (ref "J1") (pin "41") (pinfunction "41_41") (pintype "passive"))
    )
    (net (code "84") (name "ID_SC") (class "Default")
      (node (ref "J1") (pin "35") (pinfunction "35_35") (pintype "passive"))
    )
    (net (code "85") (name "ID_SD") (class "Default")
      (node (ref "J1") (pin "36") (pinfunction "36_36") (pintype "passive"))
    )
    (net (code "86") (name "Net-(D1-A)") (class "Default")
      (node (ref "D1") (pin "2") (pinfunction "A_2") (pintype "passive"))
      (node (ref "Q1") (pin "3") (pinfunction "D_3") (pintype "passive"))
      (node (ref "R1") (pin "1") (pinfunction "1_1") (pintype "passive"))
    )
    (net (code "87") (name "Net-(D2-A)") (class "Default")
      (node (ref "D2") (pin "2") (pinfunction "A_2") (pintype "passive"))
      (node (ref "Q2") (pin "3") (pinfunction "D_3") (pintype "passive"))
      (node (ref "R2") (pin "1") (pinfunction "1_1") (pintype "passive"))
    )
    (net (code "88") (name "Net-(D3-A)") (class "Default")
      (node (ref "D3") (pin "2") (pinfunction "A_2") (pintype "passive"))
      (node (ref "Q3") (pin "3") (pinfunction "D_3") (pintype "passive"))
      (node (ref "R5") (pin "1") (pinfunction "1_1") (pintype "passive"))
    )
    (net (code "89") (name "Net-(D4-A)") (class "Default")
      (node (ref "D4") (pin "2") (pinfunction "A_2") (pintype "passive"))
      (node (ref "Q4") (pin "3") (pinfunction "D_3") (pintype "passive"))
      (node (ref "R6") (pin "1") (pinfunction "1_1") (pintype "passive"))
    )
    (net (code "90") (name "Net-(LED1-K)") (class "Default")
      (node (ref "LED1") (pin "1") (pinfunction "K_1") (pintype "passive"))
      (node (ref "R13") (pin "2") (pinfunction "2_2") (pintype "passive"))
    )
    (net (code "91") (name "Net-(LED2-K)") (class "Default")
      (node (ref "LED2") (pin "2") (pinfunction "K_2") (pintype "passive"))
      (node (ref "R14") (pin "2") (pinfunction "2_2") (pintype "passive"))
    )
    (net (code "92") (name "Net-(LED3-K)") (class "Default")
      (node (ref "LED3") (pin "2") (pinfunction "K_2") (pintype "passive"))
      (node (ref "R15") (pin "2") (pinfunction "2_2") (pintype "passive"))
    )
    (net (code "93") (name "Net-(LED4-K)") (class "Default")
      (node (ref "LED4") (pin "2") (pinfunction "K_2") (pintype "passive"))
      (node (ref "R16") (pin "2") (pinfunction "2_2") (pintype "passive"))
    )
    (net (code "94") (name "Net-(LED5-K)") (class "Default")
      (node (ref "LED5") (pin "1") (pinfunction "K_1") (pintype "passive"))
      (node (ref "R17") (pin "2") (pinfunction "2_2") (pintype "passive"))
    )
    (net (code "95") (name "Net-(Q1-G)") (class "Default")
      (node (ref "Q1") (pin "1") (pinfunction "G_1") (pintype "passive"))
      (node (ref "R3") (pin "2") (pinfunction "2_2") (pintype "passive"))
    )
    (net (code "96") (name "Net-(Q2-G)") (class "Default")
      (node (ref "Q2") (pin "1") (pinfunction "G_1") (pintype "passive"))
      (node (ref "R4") (pin "2") (pinfunction "2_2") (pintype "passive"))
    )
    (net (code "97") (name "Net-(Q3-G)") (class "Default")
      (node (ref "Q3") (pin "1") (pinfunction "G_1") (pintype "passive"))
      (node (ref "R7") (pin "2") (pinfunction "2_2") (pintype "passive"))
    )
    (net (code "98") (name "Net-(Q4-G)") (class "Default")
      (node (ref "Q4") (pin "1") (pinfunction "G_1") (pintype "passive"))
      (node (ref "R8") (pin "2") (pinfunction "2_2") (pintype "passive"))
    )
    (net (code "99") (name "Net-(R9-Pad1)") (class "Default")
      (node (ref "R9") (pin "1") (pinfunction "1_1") (pintype "passive"))
      (node (ref "W2") (pin "2") (pinfunction "2_2") (pintype "passive"))
    )
    (net (code "100") (name "Net-(R10-Pad1)") (class "Default")
      (node (ref "R10") (pin "1") (pinfunction "1_1") (pintype "passive"))
      (node (ref "W1") (pin "2") (pinfunction "2_2") (pintype "passive"))
    )
    (net (code "101") (name "Net-(R18-Pad2)") (class "Default")
      (node (ref "R18") (pin "2") (pinfunction "2_2") (pintype "passive"))
      (node (ref "W3") (pin "1") (pinfunction "1_1") (pintype "passive"))
    )
    (net (code "102") (name "Net-(R19-Pad2)") (class "Default")
      (node (ref "R19") (pin "2") (pinfunction "2_2") (pintype "passive"))
      (node (ref "W4") (pin "1") (pinfunction "1_1") (pintype "passive"))
    )
    (net (code "103") (name "PCIE_CLK_N") (class "Default")
      (node (ref "J2") (pin "12") (pinfunction "12_12") (pintype "passive"))
    )
    (net (code "104") (name "PCIE_CLK_P") (class "Default")
      (node (ref "J2") (pin "10") (pinfunction "10_10") (pintype "passive"))
    )
    (net (code "105") (name "PCIE_PWR_EN") (class "Default")
      (node (ref "J2") (pin "6") (pinfunction "6_6") (pintype "passive"))
    )
    (net (code "106") (name "PCIE_RX_N") (class "Default")
      (node (ref "J2") (pin "18") (pinfunction "18_18") (pintype "passive"))
    )
    (net (code "107") (name "PCIE_RX_P") (class "Default")
      (node (ref "J2") (pin "16") (pinfunction "16_16") (pintype "passive"))
    )
    (net (code "108") (name "PCIE_TX_N") (class "Default")
      (node (ref "J2") (pin "24") (pinfunction "24_24") (pintype "passive"))
    )
    (net (code "109") (name "PCIE_TX_P") (class "Default")
      (node (ref "J2") (pin "22") (pinfunction "22_22") (pintype "passive"))
    )
    (net (code "110") (name "PCIE_nCLKREQ") (class "Default")
      (node (ref "J2") (pin "2") (pinfunction "2_2") (pintype "passive"))
    )
    (net (code "111") (name "PCIE_nRST") (class "Default")
      (node (ref "J2") (pin "9") (pinfunction "9_9") (pintype "passive"))
    )
    (net (code "112") (name "PCIE_nWAKE") (class "Default")
      (node (ref "J2") (pin "4") (pinfunction "4_4") (pintype "passive"))
    )
    (net (code "113") (name "SCL0") (class "Default")
      (node (ref "J1") (pin "80") (pinfunction "80_80") (pintype "passive"))
    )
    (net (code "114") (name "SDA0") (class "Default")
      (node (ref "J1") (pin "82") (pinfunction "82_82") (pintype "passive"))
    )
    (net (code "115") (name "USB2_Bat_D_N") (class "Default")
      (node (ref "J2") (pin "36") (pinfunction "36_36") (pintype "passive"))
    )
    (net (code "116") (name "USB2_Bat_D_P") (class "Default")
      (node (ref "J2") (pin "34") (pinfunction "34_34") (pintype "passive"))
    )
    (net (code "117") (name "USB2_D_N") (class "Default")
      (node (ref "J2") (pin "3") (pinfunction "3_3") (pintype "passive"))
    )
    (net (code "118") (name "USB2_D_P") (class "Default")
      (node (ref "J2") (pin "5") (pinfunction "5_5") (pintype "passive"))
    )
    (net (code "119") (name "USB2_Power_D_N") (class "Default")
      (node (ref "J2") (pin "65") (pinfunction "65_65") (pintype "passive"))
    )
    (net (code "120") (name "USB2_Power_D_P") (class "Default")
      (node (ref "J2") (pin "63") (pinfunction "63_63") (pintype "passive"))
    )
    (net (code "121") (name "USB3-0-RX_N") (class "Default")
      (node (ref "J2") (pin "28") (pinfunction "28_28") (pintype "passive"))
    )
    (net (code "122") (name "USB3-0-RX_P") (class "Default")
      (node (ref "J2") (pin "30") (pinfunction "30_30") (pintype "passive"))
    )
    (net (code "123") (name "USB3-0-TX_N") (class "Default")
      (node (ref "J2") (pin "40") (pinfunction "40_40") (pintype "passive"))
    )
    (net (code "124") (name "USB3-0-TX_P") (class "Default")
      (node (ref "J2") (pin "42") (pinfunction "42_42") (pintype "passive"))
    )
    (net (code "125") (name "USB3-1-RX_N") (class "Default")
      (node (ref "J2") (pin "57") (pinfunction "57_57") (pintype "passive"))
    )
    (net (code "126") (name "USB3-1-RX_P") (class "Default")
      (node (ref "J2") (pin "59") (pinfunction "59_59") (pintype "passive"))
    )
    (net (code "127") (name "USB3-1-TX_N") (class "Default")
      (node (ref "J2") (pin "69") (pinfunction "69_69") (pintype "passive"))
    )
    (net (code "128") (name "USB3-1-TX_P") (class "Default")
      (node (ref "J2") (pin "71") (pinfunction "71_71") (pintype "passive"))
    )
    (net (code "129") (name "VBAT") (class "Default")
      (node (ref "J1") (pin "76") (pinfunction "76_76") (pintype "passive"))
      (node (ref "J3") (pin "1") (pinfunction "1_1") (pintype "passive"))
    )
    (net (code "130") (name "VCC_USB_Bat") (class "Default")
      (node (ref "LED3") (pin "1") (pinfunction "A_1") (pintype "passive"))
    )
    (net (code "131") (name "VCC_USB_Power") (class "Default")
      (node (ref "LED4") (pin "1") (pinfunction "A_1") (pintype "passive"))
    )
    (net (code "132") (name "unconnected-(IC1-~{FLG}-Pad3)") (class "Default")
      (node (ref "IC1") (pin "3") (pinfunction "~{FLG}_3") (pintype "passive+no_connect"))
    )
    (net (code "133") (name "unconnected-(J1-Pad18)") (class "Default")
      (node (ref "J1") (pin "18") (pinfunction "18_18") (pintype "passive+no_connect"))
    )
    (net (code "134") (name "unconnected-(J1-Pad20)") (class "Default")
      (node (ref "J1") (pin "20") (pinfunction "20_20") (pintype "passive+no_connect"))
    )
    (net (code "135") (name "unconnected-(J1-Pad42)") (class "Default")
      (node (ref "J1") (pin "42") (pinfunction "42_42") (pintype "passive"))
    )
    (net (code "136") (name "unconnected-(J1-Pad64)") (class "Default")
      (node (ref "J1") (pin "64") (pinfunction "64_64") (pintype "passive+no_connect"))
    )
    (net (code "137") (name "unconnected-(J1-Pad68)") (class "Default")
      (node (ref "J1") (pin "68") (pinfunction "68_68") (pintype "passive+no_connect"))
    )
    (net (code "138") (name "unconnected-(J1-Pad70)") (class "Default")
      (node (ref "J1") (pin "70") (pinfunction "70_70") (pintype "passive+no_connect"))
    )
    (net (code "139") (name "unconnected-(J1-Pad72)") (class "Default")
      (node (ref "J1") (pin "72") (pinfunction "72_72") (pintype "passive+no_connect"))
    )
    (net (code "140") (name "unconnected-(J1-Pad73)") (class "Default")
      (node (ref "J1") (pin "73") (pinfunction "73_73") (pintype "passive+no_connect"))
    )
    (net (code "141") (name "unconnected-(J1-Pad89)") (class "Default")
      (node (ref "J1") (pin "89") (pinfunction "89_89") (pintype "passive+no_connect"))
    )
    (net (code "142") (name "unconnected-(J1-Pad91)") (class "Default")
      (node (ref "J1") (pin "91") (pinfunction "91_91") (pintype "passive+no_connect"))
    )
    (net (code "143") (name "unconnected-(J1-Pad93)") (class "Default")
      (node (ref "J1") (pin "93") (pinfunction "93_93") (pintype "passive+no_connect"))
    )
    (net (code "144") (name "unconnected-(J1-Pad94)") (class "Default")
      (node (ref "J1") (pin "94") (pinfunction "94_94") (pintype "passive+no_connect"))
    )
    (net (code "145") (name "unconnected-(J1-Pad95)") (class "Default")
      (node (ref "J1") (pin "95") (pinfunction "95_95") (pintype "passive+no_connect"))
    )
    (net (code "146") (name "unconnected-(J1-Pad96)") (class "Default")
      (node (ref "J1") (pin "96") (pinfunction "96_96") (pintype "passive+no_connect"))
    )
    (net (code "147") (name "unconnected-(J1-Pad99)") (class "Default")
      (node (ref "J1") (pin "99") (pinfunction "99_99") (pintype "passive+no_connect"))
    )
    (net (code "148") (name "unconnected-(J2-Pad11)") (class "Default")
      (node (ref "J2") (pin "11") (pinfunction "11_11") (pintype "passive+no_connect"))
    )
    (net (code "149") (name "unconnected-(J2-Pad43)") (class "Default")
      (node (ref "J2") (pin "43") (pinfunction "43_43") (pintype "passive+no_connect"))
    )
    (net (code "150") (name "unconnected-(J2-Pad45)") (class "Default")
      (node (ref "J2") (pin "45") (pinfunction "45_45") (pintype "passive+no_connect"))
    )
    (net (code "151") (name "unconnected-(J2-Pad46)") (class "Default")
      (node (ref "J2") (pin "46") (pinfunction "46_46") (pintype "passive+no_connect"))
    )
    (net (code "152") (name "unconnected-(J2-Pad47)") (class "Default")
      (node (ref "J2") (pin "47") (pinfunction "47_47") (pintype "passive+no_connect"))
    )
    (net (code "153") (name "unconnected-(J2-Pad48)") (class "Default")
      (node (ref "J2") (pin "48") (pinfunction "48_48") (pintype "passive+no_connect"))
    )
    (net (code "154") (name "unconnected-(J2-Pad49)") (class "Default")
      (node (ref "J2") (pin "49") (pinfunction "49_49") (pintype "passive+no_connect"))
    )
    (net (code "155") (name "unconnected-(J2-Pad52)") (class "Default")
      (node (ref "J2") (pin "52") (pinfunction "52_52") (pintype "passive+no_connect"))
    )
    (net (code "156") (name "unconnected-(J2-Pad54)") (class "Default")
      (node (ref "J2") (pin "54") (pinfunction "54_54") (pintype "passive+no_connect"))
    )
    (net (code "157") (name "unconnected-(J2-Pad58)") (class "Default")
      (node (ref "J2") (pin "58") (pinfunction "58_58") (pintype "passive+no_connect"))
    )
    (net (code "158") (name "unconnected-(J2-Pad60)") (class "Default")
      (node (ref "J2") (pin "60") (pinfunction "60_60") (pintype "passive+no_connect"))
    )
    (net (code "159") (name "unconnected-(J2-Pad64)") (class "Default")
      (node (ref "J2") (pin "64") (pinfunction "64_64") (pintype "passive+no_connect"))
    )
    (net (code "160") (name "unconnected-(J2-Pad66)") (class "Default")
      (node (ref "J2") (pin "66") (pinfunction "66_66") (pintype "passive+no_connect"))
    )
    (net (code "161") (name "unconnected-(J2-Pad93)") (class "Default")
      (node (ref "J2") (pin "93") (pinfunction "93_93") (pintype "passive+no_connect"))
    )
    (net (code "162") (name "unconnected-(J2-Pad94)") (class "Default")
      (node (ref "J2") (pin "94") (pinfunction "94_94") (pintype "passive+no_connect"))
    )
    (net (code "163") (name "unconnected-(J2-Pad95)") (class "Default")
      (node (ref "J2") (pin "95") (pinfunction "95_95") (pintype "passive+no_connect"))
    )
    (net (code "164") (name "unconnected-(J2-Pad96)") (class "Default")
      (node (ref "J2") (pin "96") (pinfunction "96_96") (pintype "passive+no_connect"))
    )
    (net (code "165") (name "unconnected-(SD1-Pad9)") (class "Default")
      (node (ref "SD1") (pin "9") (pinfunction "9_9") (pintype "passive+no_connect"))
    )
    (net (code "166") (name "unconnected-(SD1-Pad10)") (class "Default")
      (node (ref "SD1") (pin "10") (pinfunction "10_10") (pintype "passive+no_connect"))
    )
  )
)
